# trackduino_nano.net
KiCad netlist of a schematic drawn in EAGLE
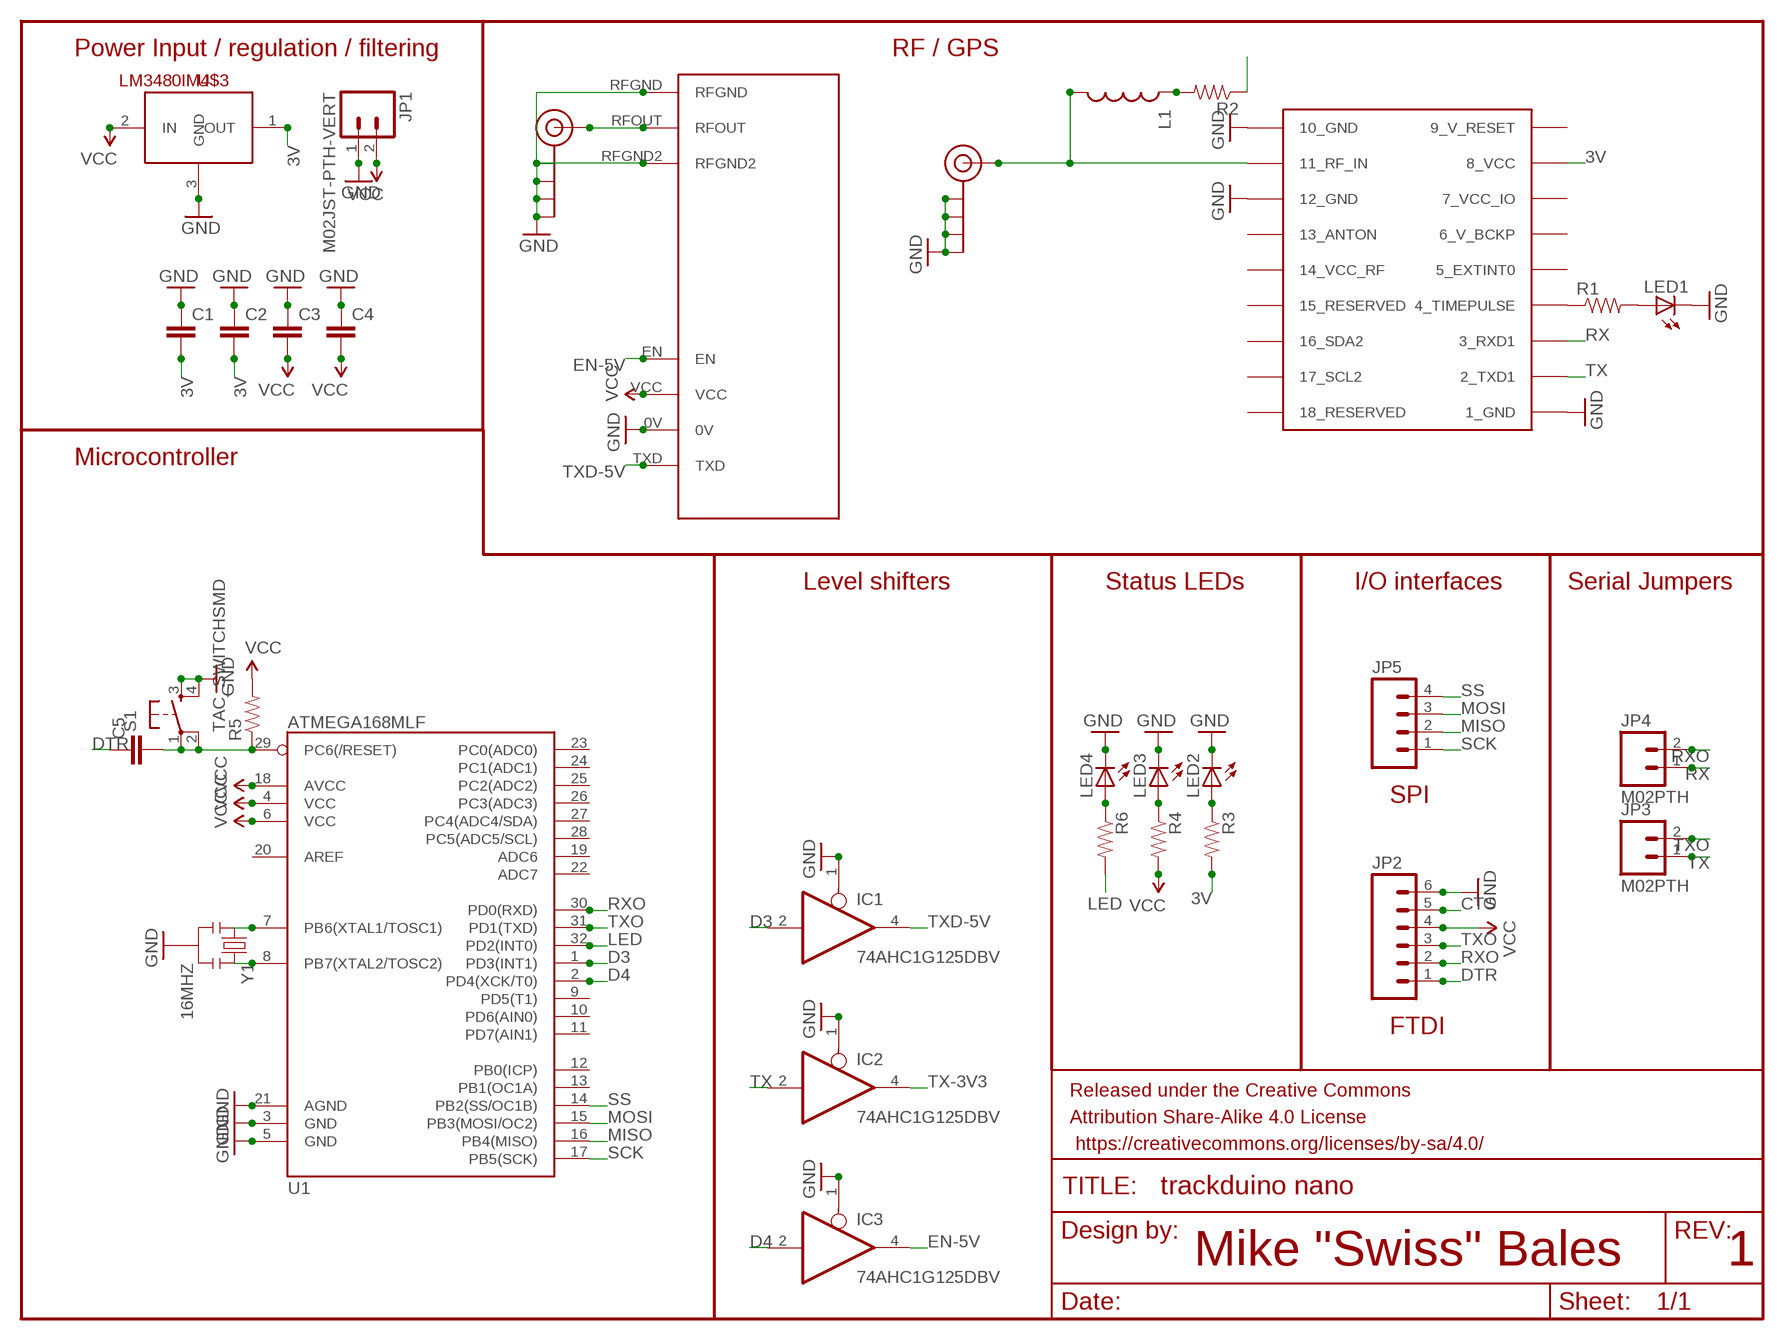
[diagram p0: schematic, sheet 1]

(export (version "E")
  (design (tool "Eeschema 10.0.6"))
  (components
    (comp (ref "C1")
      (value "CAP0805")
      (footprint "eagle-import:0805")
      (libsource (lib "eagle-import") (part "CAP0805"))
    )
    (comp (ref "C2")
      (value "CAP0805")
      (footprint "eagle-import:0805")
      (libsource (lib "eagle-import") (part "CAP0805"))
    )
    (comp (ref "C3")
      (value "CAP0805")
      (footprint "eagle-import:0805")
      (libsource (lib "eagle-import") (part "CAP0805"))
    )
    (comp (ref "C4")
      (value "CAP0805")
      (footprint "eagle-import:0805")
      (libsource (lib "eagle-import") (part "CAP0805"))
    )
    (comp (ref "C5")
      (value "CAP0805")
      (footprint "eagle-import:0805")
      (libsource (lib "eagle-import") (part "CAP0805"))
    )
    (comp (ref "FRAME1")
      (value "FRAME-LETTER")
      (footprint "eagle-import:CREATIVE_COMMONS")
      (libsource (lib "eagle-import") (part "FRAME-LETTER"))
    )
    (comp (ref "IC1")
      (value "74AHC1G125DBV")
      (footprint "eagle-import:SOT23-5")
      (libsource (lib "eagle-import") (part "741G125DBVAHC"))
    )
    (comp (ref "IC2")
      (value "74AHC1G125DBV")
      (footprint "eagle-import:SOT23-5")
      (libsource (lib "eagle-import") (part "741G125DBVAHC"))
    )
    (comp (ref "IC3")
      (value "74AHC1G125DBV")
      (footprint "eagle-import:SOT23-5")
      (libsource (lib "eagle-import") (part "741G125DBVAHC"))
    )
    (comp (ref "J$1")
      (value "SMA_EDGE")
      (footprint "eagle-import:SMA-EDGE")
      (libsource (lib "eagle-import") (part "SMA_EDGE"))
    )
    (comp (ref "J$2")
      (value "SMA_EDGE")
      (footprint "eagle-import:SMA-EDGE")
      (libsource (lib "eagle-import") (part "SMA_EDGE"))
    )
    (comp (ref "JP1")
      (value "M02JST-PTH-VERT")
      (footprint "eagle-import:JST-2-PTH-VERT")
      (libsource (lib "eagle-import") (part "M02JST-PTH-VERT"))
    )
    (comp (ref "JP2")
      (value "M06NO_SILK_FEMALE_PTH")
      (footprint "eagle-import:1X06_NO_SILK")
      (libsource (lib "eagle-import") (part "M06NO_SILK_FEMALE_PTH"))
    )
    (comp (ref "JP3")
      (value "M02PTH")
      (footprint "eagle-import:1X02")
      (libsource (lib "eagle-import") (part "M02PTH"))
    )
    (comp (ref "JP4")
      (value "M02PTH")
      (footprint "eagle-import:1X02")
      (libsource (lib "eagle-import") (part "M02PTH"))
    )
    (comp (ref "JP5")
      (value "M041X04_NO_SILK")
      (footprint "eagle-import:1X04_NO_SILK")
      (libsource (lib "eagle-import") (part "M041X04_NO_SILK"))
    )
    (comp (ref "L1")
      (value "INDUCTOR0805")
      (footprint "eagle-import:0805")
      (libsource (lib "eagle-import") (part "INDUCTOR0805"))
    )
    (comp (ref "LED1")
      (value "LEDCHIP-LED0805")
      (footprint "eagle-import:CHIP-LED0805")
      (libsource (lib "eagle-import") (part "LEDCHIP-LED0805"))
    )
    (comp (ref "LED2")
      (value "LEDCHIP-LED0805")
      (footprint "eagle-import:CHIP-LED0805")
      (libsource (lib "eagle-import") (part "LEDCHIP-LED0805"))
    )
    (comp (ref "LED3")
      (value "LEDCHIP-LED0805")
      (footprint "eagle-import:CHIP-LED0805")
      (libsource (lib "eagle-import") (part "LEDCHIP-LED0805"))
    )
    (comp (ref "LED4")
      (value "LEDCHIP-LED0805")
      (footprint "eagle-import:CHIP-LED0805")
      (libsource (lib "eagle-import") (part "LEDCHIP-LED0805"))
    )
    (comp (ref "R1")
      (value "RESISTOR0805-RES")
      (footprint "eagle-import:0805")
      (libsource (lib "eagle-import") (part "RESISTOR0805-RES"))
    )
    (comp (ref "R2")
      (value "RESISTOR0805-RES")
      (footprint "eagle-import:0805")
      (libsource (lib "eagle-import") (part "RESISTOR0805-RES"))
    )
    (comp (ref "R3")
      (value "RESISTOR0805-RES")
      (footprint "eagle-import:0805")
      (libsource (lib "eagle-import") (part "RESISTOR0805-RES"))
    )
    (comp (ref "R4")
      (value "RESISTOR0805-RES")
      (footprint "eagle-import:0805")
      (libsource (lib "eagle-import") (part "RESISTOR0805-RES"))
    )
    (comp (ref "R5")
      (value "RESISTOR0805-RES")
      (footprint "eagle-import:0805")
      (libsource (lib "eagle-import") (part "RESISTOR0805-RES"))
    )
    (comp (ref "R6")
      (value "RESISTOR0805-RES")
      (footprint "eagle-import:0805")
      (libsource (lib "eagle-import") (part "RESISTOR0805-RES"))
    )
    (comp (ref "S1")
      (value "TAC_SWITCHSMD")
      (footprint "eagle-import:TACTILE-SWITCH-SMD")
      (libsource (lib "eagle-import") (part "TAC_SWITCHSMD"))
    )
    (comp (ref "U$1")
      (value "UBLOX_MAX")
      (footprint "eagle-import:UBLOX_MAX")
      (libsource (lib "eagle-import") (part "UBLOX_MAX"))
    )
    (comp (ref "U$2")
      (value "RADIOMETRIX-HX1")
      (footprint "eagle-import:RADIOMETRIX-HX1")
      (libsource (lib "eagle-import") (part "RADIOMETRIX-HX1"))
    )
    (comp (ref "U$3")
      (value "LM3480IM4")
      (footprint "eagle-import:SOT23-3")
      (libsource (lib "eagle-import") (part "LM3480IM4"))
    )
    (comp (ref "U1")
      (value "ATMEGA168MLF")
      (footprint "eagle-import:MLF32")
      (libsource (lib "eagle-import") (part "ATMEGA168MLF"))
    )
    (comp (ref "Y1")
      (value "16MHZ")
      (footprint "eagle-import:RESONATOR-SMD")
      (libsource (lib "eagle-import") (part "RESONATOR16MHZ"))
    )
  )
  (nets
    (net (code "1") (name "/3V") (class "Default")
      (node (ref "C1") (pin "2") (pinfunction "2_2") (pintype "passive"))
      (node (ref "C2") (pin "2") (pinfunction "2_2") (pintype "passive"))
      (node (ref "R3") (pin "2") (pinfunction "2_2") (pintype "passive"))
      (node (ref "U$1") (pin "8_VCC") (pinfunction "8_VCC_8_VCC") (pintype "power_in"))
      (node (ref "U$3") (pin "1") (pinfunction "OUT_1") (pintype "bidirectional"))
    )
    (net (code "2") (name "/7_VCC_IO") (class "Default")
      (node (ref "U$1") (pin "7_VCC_IO") (pinfunction "7_VCC_IO_7_VCC_IO") (pintype "power_in"))
    )
    (net (code "3") (name "/9_V_RESET") (class "Default")
      (node (ref "U$1") (pin "9_V_RESET") (pinfunction "9_V_RESET_9_V_RESET") (pintype "power_in"))
    )
    (net (code "4") (name "/CTS") (class "Default")
      (node (ref "JP2") (pin "5") (pinfunction "5_5") (pintype "passive"))
    )
    (net (code "5") (name "/D3") (class "Default")
      (node (ref "IC1") (pin "2") (pinfunction "I_2") (pintype "input"))
      (node (ref "U1") (pin "1") (pinfunction "PD3(INT1)_1") (pintype "bidirectional"))
    )
    (net (code "6") (name "/D4") (class "Default")
      (node (ref "IC3") (pin "2") (pinfunction "I_2") (pintype "input"))
      (node (ref "U1") (pin "2") (pinfunction "PD4(XCK/T0)_2") (pintype "bidirectional"))
    )
    (net (code "7") (name "/DTR") (class "Default")
      (node (ref "C5") (pin "1") (pinfunction "1_1") (pintype "passive"))
      (node (ref "JP2") (pin "1") (pinfunction "1_1") (pintype "passive"))
    )
    (net (code "8") (name "/EN-5V") (class "Default")
      (node (ref "IC3") (pin "4") (pinfunction "O_4") (pintype "tri_state"))
      (node (ref "U$2") (pin "EN") (pinfunction "EN_EN") (pintype "bidirectional"))
    )
    (net (code "9") (name "/LED") (class "Default")
      (node (ref "R6") (pin "2") (pinfunction "2_2") (pintype "passive"))
      (node (ref "U1") (pin "32") (pinfunction "PD2(INT0)_32") (pintype "bidirectional"))
    )
    (net (code "10") (name "/MISO") (class "Default")
      (node (ref "JP5") (pin "2") (pinfunction "2_2") (pintype "passive"))
      (node (ref "U1") (pin "16") (pinfunction "PB4(MISO)_16") (pintype "bidirectional"))
    )
    (net (code "11") (name "/MOSI") (class "Default")
      (node (ref "JP5") (pin "3") (pinfunction "3_3") (pintype "passive"))
      (node (ref "U1") (pin "15") (pinfunction "PB3(MOSI/OC2)_15") (pintype "bidirectional"))
    )
    (net (code "12") (name "/RX") (class "Default")
      (node (ref "JP4") (pin "1") (pinfunction "1_1") (pintype "passive"))
      (node (ref "U$1") (pin "3_RXD1") (pinfunction "3_RXD1_3_RXD1") (pintype "bidirectional"))
    )
    (net (code "13") (name "/RXO") (class "Default")
      (node (ref "JP2") (pin "2") (pinfunction "2_2") (pintype "passive"))
      (node (ref "JP4") (pin "2") (pinfunction "2_2") (pintype "passive"))
      (node (ref "U1") (pin "30") (pinfunction "PD0(RXD)_30") (pintype "bidirectional"))
    )
    (net (code "14") (name "/SCK") (class "Default")
      (node (ref "JP5") (pin "1") (pinfunction "1_1") (pintype "passive"))
      (node (ref "U1") (pin "17") (pinfunction "PB5(SCK)_17") (pintype "bidirectional"))
    )
    (net (code "15") (name "/SS") (class "Default")
      (node (ref "JP5") (pin "4") (pinfunction "4_4") (pintype "passive"))
      (node (ref "U1") (pin "14") (pinfunction "PB2(SS/OC1B)_14") (pintype "bidirectional"))
    )
    (net (code "16") (name "/TX") (class "Default")
      (node (ref "IC2") (pin "2") (pinfunction "I_2") (pintype "input"))
      (node (ref "JP3") (pin "1") (pinfunction "1_1") (pintype "passive"))
      (node (ref "U$1") (pin "2_TXD1") (pinfunction "2_TXD1_2_TXD1") (pintype "bidirectional"))
    )
    (net (code "17") (name "/TX-3V3") (class "Default")
      (node (ref "IC2") (pin "4") (pinfunction "O_4") (pintype "tri_state"))
    )
    (net (code "18") (name "/TXD-5V") (class "Default")
      (node (ref "IC1") (pin "4") (pinfunction "O_4") (pintype "tri_state"))
      (node (ref "U$2") (pin "TXD") (pinfunction "TXD_TXD") (pintype "bidirectional"))
    )
    (net (code "19") (name "/TXO") (class "Default")
      (node (ref "JP2") (pin "3") (pinfunction "3_3") (pintype "passive"))
      (node (ref "JP3") (pin "2") (pinfunction "2_2") (pintype "passive"))
      (node (ref "U1") (pin "31") (pinfunction "PD1(TXD)_31") (pintype "bidirectional"))
    )
    (net (code "20") (name "GND") (class "Default")
      (node (ref "C1") (pin "1") (pinfunction "1_1") (pintype "passive"))
      (node (ref "C2") (pin "1") (pinfunction "1_1") (pintype "passive"))
      (node (ref "C3") (pin "1") (pinfunction "1_1") (pintype "passive"))
      (node (ref "C4") (pin "1") (pinfunction "1_1") (pintype "passive"))
      (node (ref "IC1") (pin "1") (pinfunction "OE_1") (pintype "input"))
      (node (ref "IC2") (pin "1") (pinfunction "OE_1") (pintype "input"))
      (node (ref "IC3") (pin "1") (pinfunction "OE_1") (pintype "input"))
      (node (ref "J$1") (pin "GND@0") (pinfunction "GND_GND@0") (pintype "bidirectional"))
      (node (ref "J$1") (pin "GND@1") (pinfunction "GND_GND@1") (pintype "bidirectional"))
      (node (ref "J$1") (pin "GND@2") (pinfunction "GND_GND@2") (pintype "bidirectional"))
      (node (ref "J$1") (pin "GND@3") (pinfunction "GND_GND@3") (pintype "bidirectional"))
      (node (ref "J$2") (pin "GND@0") (pinfunction "GND_GND@0") (pintype "bidirectional"))
      (node (ref "J$2") (pin "GND@1") (pinfunction "GND_GND@1") (pintype "bidirectional"))
      (node (ref "J$2") (pin "GND@2") (pinfunction "GND_GND@2") (pintype "bidirectional"))
      (node (ref "J$2") (pin "GND@3") (pinfunction "GND_GND@3") (pintype "bidirectional"))
      (node (ref "JP1") (pin "1") (pinfunction "1_1") (pintype "passive"))
      (node (ref "JP2") (pin "6") (pinfunction "6_6") (pintype "passive"))
      (node (ref "LED1") (pin "C") (pinfunction "C_C") (pintype "passive"))
      (node (ref "LED2") (pin "C") (pinfunction "C_C") (pintype "passive"))
      (node (ref "LED3") (pin "C") (pinfunction "C_C") (pintype "passive"))
      (node (ref "LED4") (pin "C") (pinfunction "C_C") (pintype "passive"))
      (node (ref "S1") (pin "3") (pinfunction "3_3") (pintype "passive"))
      (node (ref "S1") (pin "4") (pinfunction "4_4") (pintype "passive"))
      (node (ref "U$1") (pin "10_GND") (pinfunction "10_GND_10_GND") (pintype "power_in"))
      (node (ref "U$1") (pin "12_GND") (pinfunction "12_GND_12_GND") (pintype "power_in"))
      (node (ref "U$1") (pin "1_GND") (pinfunction "1_GND_1_GND") (pintype "power_in"))
      (node (ref "U$2") (pin "0V") (pinfunction "0V_0V") (pintype "bidirectional"))
      (node (ref "U$2") (pin "RFGND") (pinfunction "RFGND_RFGND") (pintype "bidirectional"))
      (node (ref "U$2") (pin "RFGND2") (pinfunction "RFGND2_RFGND2") (pintype "bidirectional"))
      (node (ref "U$3") (pin "3") (pinfunction "GND_3") (pintype "bidirectional"))
      (node (ref "U1") (pin "21") (pinfunction "AGND_21") (pintype "bidirectional"))
      (node (ref "U1") (pin "3") (pinfunction "GND_3") (pintype "bidirectional"))
      (node (ref "U1") (pin "5") (pinfunction "GND_5") (pintype "bidirectional"))
      (node (ref "Y1") (pin "2") (pinfunction "2_2") (pintype "passive"))
    )
    (net (code "21") (name "Net-(J$1-SIGNAL)") (class "Default")
      (node (ref "J$1") (pin "SIG") (pinfunction "SIGNAL_SIG") (pintype "bidirectional"))
      (node (ref "U$2") (pin "RFOUT") (pinfunction "RFOUT_RFOUT") (pintype "bidirectional"))
    )
    (net (code "22") (name "Net-(J$2-SIGNAL)") (class "Default")
      (node (ref "J$2") (pin "SIG") (pinfunction "SIGNAL_SIG") (pintype "bidirectional"))
      (node (ref "L1") (pin "2") (pinfunction "2_2") (pintype "passive"))
      (node (ref "U$1") (pin "11_RF_IN") (pinfunction "11_RF_IN_11_RF_IN") (pintype "bidirectional"))
    )
    (net (code "23") (name "Net-(L1-Pad1)") (class "Default")
      (node (ref "L1") (pin "1") (pinfunction "1_1") (pintype "passive"))
      (node (ref "R2") (pin "2") (pinfunction "2_2") (pintype "passive"))
    )
    (net (code "24") (name "Net-(LED1-PadA)") (class "Default")
      (node (ref "LED1") (pin "A") (pinfunction "A_A") (pintype "passive"))
      (node (ref "R1") (pin "2") (pinfunction "2_2") (pintype "passive"))
    )
    (net (code "25") (name "Net-(LED2-PadA)") (class "Default")
      (node (ref "LED2") (pin "A") (pinfunction "A_A") (pintype "passive"))
      (node (ref "R3") (pin "1") (pinfunction "1_1") (pintype "passive"))
    )
    (net (code "26") (name "Net-(LED3-PadA)") (class "Default")
      (node (ref "LED3") (pin "A") (pinfunction "A_A") (pintype "passive"))
      (node (ref "R4") (pin "1") (pinfunction "1_1") (pintype "passive"))
    )
    (net (code "27") (name "Net-(LED4-PadA)") (class "Default")
      (node (ref "LED4") (pin "A") (pinfunction "A_A") (pintype "passive"))
      (node (ref "R6") (pin "1") (pinfunction "1_1") (pintype "passive"))
    )
    (net (code "28") (name "Net-(R1-Pad1)") (class "Default")
      (node (ref "R1") (pin "1") (pinfunction "1_1") (pintype "passive"))
      (node (ref "U$1") (pin "4_TIMEPULSE") (pinfunction "4_TIMEPULSE_4_TIMEPULSE") (pintype "bidirectional"))
    )
    (net (code "29") (name "Net-(U1-PB6(XTAL1{slash}TOSC1))") (class "Default")
      (node (ref "U1") (pin "7") (pinfunction "PB6(XTAL1/TOSC1)_7") (pintype "bidirectional"))
      (node (ref "Y1") (pin "1") (pinfunction "1_1") (pintype "passive"))
    )
    (net (code "30") (name "Net-(U1-PB7(XTAL2{slash}TOSC2))") (class "Default")
      (node (ref "U1") (pin "8") (pinfunction "PB7(XTAL2/TOSC2)_8") (pintype "bidirectional"))
      (node (ref "Y1") (pin "3") (pinfunction "3_3") (pintype "passive"))
    )
    (net (code "31") (name "Net-(U1-PC6({slash}RESET))") (class "Default")
      (node (ref "C5") (pin "2") (pinfunction "2_2") (pintype "passive"))
      (node (ref "R5") (pin "1") (pinfunction "1_1") (pintype "passive"))
      (node (ref "S1") (pin "1") (pinfunction "1_1") (pintype "passive"))
      (node (ref "S1") (pin "2") (pinfunction "2_2") (pintype "passive"))
      (node (ref "U1") (pin "29") (pinfunction "PC6(/RESET)_29") (pintype "bidirectional"))
    )
    (net (code "32") (name "VCC") (class "Default")
      (node (ref "C3") (pin "2") (pinfunction "2_2") (pintype "passive"))
      (node (ref "C4") (pin "2") (pinfunction "2_2") (pintype "passive"))
      (node (ref "JP1") (pin "2") (pinfunction "2_2") (pintype "passive"))
      (node (ref "JP2") (pin "4") (pinfunction "4_4") (pintype "passive"))
      (node (ref "R4") (pin "2") (pinfunction "2_2") (pintype "passive"))
      (node (ref "R5") (pin "2") (pinfunction "2_2") (pintype "passive"))
      (node (ref "U$2") (pin "VCC") (pinfunction "VCC_VCC") (pintype "bidirectional"))
      (node (ref "U$3") (pin "2") (pinfunction "IN_2") (pintype "bidirectional"))
      (node (ref "U1") (pin "18") (pinfunction "AVCC_18") (pintype "bidirectional"))
      (node (ref "U1") (pin "4") (pinfunction "VCC_4") (pintype "bidirectional"))
      (node (ref "U1") (pin "6") (pinfunction "VCC_6") (pintype "bidirectional"))
    )
    (net (code "33") (name "unconnected-(R2-Pad1)") (class "Default")
      (node (ref "R2") (pin "1") (pinfunction "1_1") (pintype "passive"))
    )
    (net (code "34") (name "unconnected-(U$1-Pad5_EXTINT0)") (class "Default")
      (node (ref "U$1") (pin "5_EXTINT0") (pinfunction "5_EXTINT0_5_EXTINT0") (pintype "bidirectional"))
    )
    (net (code "35") (name "unconnected-(U$1-Pad6_V_BCKP)") (class "Default")
      (node (ref "U$1") (pin "6_V_BCKP") (pinfunction "6_V_BCKP_6_V_BCKP") (pintype "bidirectional"))
    )
    (net (code "36") (name "unconnected-(U$1-Pad13_ANTON)") (class "Default")
      (node (ref "U$1") (pin "13_ANTON") (pinfunction "13_ANTON_13_ANTON") (pintype "bidirectional"))
    )
    (net (code "37") (name "unconnected-(U$1-Pad14_VCC_RF)") (class "Default")
      (node (ref "U$1") (pin "14_VCC_RF") (pinfunction "14_VCC_RF_14_VCC_RF") (pintype "bidirectional"))
    )
    (net (code "38") (name "unconnected-(U$1-Pad15_RESERVED)") (class "Default")
      (node (ref "U$1") (pin "15_RESERVED") (pinfunction "15_RESERVED_15_RESERVED") (pintype "bidirectional"))
    )
    (net (code "39") (name "unconnected-(U$1-Pad16_SDA2)") (class "Default")
      (node (ref "U$1") (pin "16_SDA2") (pinfunction "16_SDA2_16_SDA2") (pintype "bidirectional"))
    )
    (net (code "40") (name "unconnected-(U$1-Pad17_SCL2)") (class "Default")
      (node (ref "U$1") (pin "17_SCL2") (pinfunction "17_SCL2_17_SCL2") (pintype "bidirectional"))
    )
    (net (code "41") (name "unconnected-(U$1-Pad18_RESERVED)") (class "Default")
      (node (ref "U$1") (pin "18_RESERVED") (pinfunction "18_RESERVED_18_RESERVED") (pintype "bidirectional"))
    )
    (net (code "42") (name "unconnected-(U1-ADC6-Pad19)") (class "Default")
      (node (ref "U1") (pin "19") (pinfunction "ADC6_19") (pintype "bidirectional"))
    )
    (net (code "43") (name "unconnected-(U1-ADC7-Pad22)") (class "Default")
      (node (ref "U1") (pin "22") (pinfunction "ADC7_22") (pintype "bidirectional"))
    )
    (net (code "44") (name "unconnected-(U1-AREF-Pad20)") (class "Default")
      (node (ref "U1") (pin "20") (pinfunction "AREF_20") (pintype "bidirectional"))
    )
    (net (code "45") (name "unconnected-(U1-PB0(ICP)-Pad12)") (class "Default")
      (node (ref "U1") (pin "12") (pinfunction "PB0(ICP)_12") (pintype "bidirectional"))
    )
    (net (code "46") (name "unconnected-(U1-PB1(OC1A)-Pad13)") (class "Default")
      (node (ref "U1") (pin "13") (pinfunction "PB1(OC1A)_13") (pintype "bidirectional"))
    )
    (net (code "47") (name "unconnected-(U1-PC0(ADC0)-Pad23)") (class "Default")
      (node (ref "U1") (pin "23") (pinfunction "PC0(ADC0)_23") (pintype "bidirectional"))
    )
    (net (code "48") (name "unconnected-(U1-PC1(ADC1)-Pad24)") (class "Default")
      (node (ref "U1") (pin "24") (pinfunction "PC1(ADC1)_24") (pintype "bidirectional"))
    )
    (net (code "49") (name "unconnected-(U1-PC2(ADC2)-Pad25)") (class "Default")
      (node (ref "U1") (pin "25") (pinfunction "PC2(ADC2)_25") (pintype "bidirectional"))
    )
    (net (code "50") (name "unconnected-(U1-PC3(ADC3)-Pad26)") (class "Default")
      (node (ref "U1") (pin "26") (pinfunction "PC3(ADC3)_26") (pintype "bidirectional"))
    )
    (net (code "51") (name "unconnected-(U1-PC4(ADC4{slash}SDA)-Pad27)") (class "Default")
      (node (ref "U1") (pin "27") (pinfunction "PC4(ADC4/SDA)_27") (pintype "bidirectional"))
    )
    (net (code "52") (name "unconnected-(U1-PC5(ADC5{slash}SCL)-Pad28)") (class "Default")
      (node (ref "U1") (pin "28") (pinfunction "PC5(ADC5/SCL)_28") (pintype "bidirectional"))
    )
    (net (code "53") (name "unconnected-(U1-PD5(T1)-Pad9)") (class "Default")
      (node (ref "U1") (pin "9") (pinfunction "PD5(T1)_9") (pintype "bidirectional"))
    )
    (net (code "54") (name "unconnected-(U1-PD6(AIN0)-Pad10)") (class "Default")
      (node (ref "U1") (pin "10") (pinfunction "PD6(AIN0)_10") (pintype "bidirectional"))
    )
    (net (code "55") (name "unconnected-(U1-PD7(AIN1)-Pad11)") (class "Default")
      (node (ref "U1") (pin "11") (pinfunction "PD7(AIN1)_11") (pintype "bidirectional"))
    )
  )
)
